# PMOD_RS485.net
KiCad netlist of a schematic drawn in Altium Designer
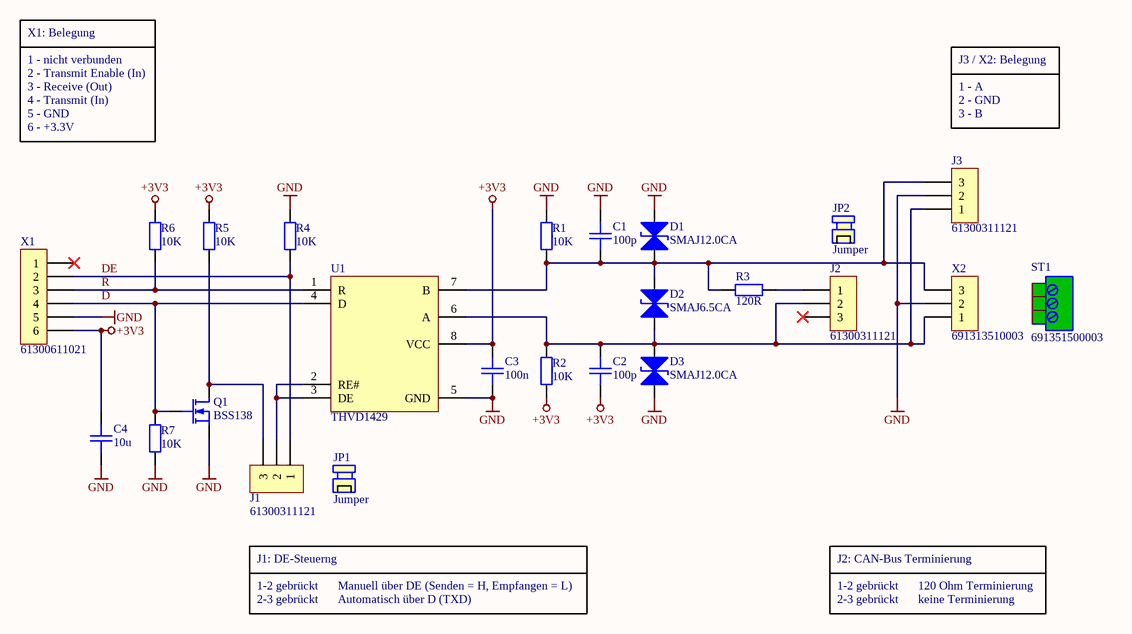
[diagram p0: PMOD_RS485.SchDoc]

(export (version "E")
  (design (tool "Eeschema 10.0.6"))
  (components
    (comp (ref "C1")
      (value "100p")
      (footprint "0805-C")
      (description "CAP CER 100PF 250V C0G/NP0 0805")
      (fields
        (field (name "MANUFACTURER PARTNO") "GRM21A5C2E101FW01D")
        (field (name "MANUFACTURER") "Murata Electronics")
      )
      (libsource (lib "Dual-CAN-HAT") (part "Capacitor 100p 0805"))
    )
    (comp (ref "C2")
      (value "100p")
      (footprint "0805-C")
      (description "CAP CER 100PF 250V C0G/NP0 0805")
      (fields
        (field (name "MANUFACTURER PARTNO") "GRM21A5C2E101FW01D")
        (field (name "MANUFACTURER") "Murata Electronics")
      )
      (libsource (lib "Dual-CAN-HAT") (part "Capacitor 100p 0805"))
    )
    (comp (ref "C3")
      (value "100n")
      (footprint "0805-C")
      (description "CAP CER 0.1UF 50V X8R 0805")
      (fields
        (field (name "MANUFACTURER PARTNO") "GCM21BR91H104KA37L")
        (field (name "MANUFACTURER") "Murata Electronics")
      )
      (libsource (lib "Dual-CAN-HAT") (part "Capacitor 100n 0805"))
    )
    (comp (ref "C4")
      (value "10u")
      (footprint "0805-C")
      (description "CAP CER 10UF 16V X5R 0805")
      (fields
        (field (name "MANUFACTURER PARTNO") "EMK212BBJ106KGHT")
        (field (name "MANUFACTURER") "Taiyo Yuden")
      )
      (libsource (lib "Dual-CAN-HAT") (part "Capacitor 10u 0805"))
    )
    (comp (ref "D1")
      (value "SMAJ12.0CA")
      (footprint "SMA-BIDIRECTIONAL")
      (description "TVS DIODE 12V 19.9V DO214AC")
      (fields
        (field (name "MANUFACTURER PARTNO") "SMAJ12CA-TP")
        (field (name "MANUFACTURER") "Micro Commercial Co")
      )
      (libsource (lib "Dual-CAN-HAT") (part "Diode TVS SMAJ12.0CA"))
    )
    (comp (ref "D2")
      (value "SMAJ6.5CA")
      (footprint "SMA-BIDIRECTIONAL")
      (description "TVS DIODE 6.5V 11.2V DO214AC")
      (fields
        (field (name "MANUFACTURER PARTNO") "SMAJ6.5CA-TP")
        (field (name "MANUFACTURER") "Micro Commercial Co")
      )
      (libsource (lib "Dual-CAN-HAT") (part "Diode TVS SMAJ6.5CA"))
    )
    (comp (ref "D3")
      (value "SMAJ12.0CA")
      (footprint "SMA-BIDIRECTIONAL")
      (description "TVS DIODE 12V 19.9V DO214AC")
      (fields
        (field (name "MANUFACTURER PARTNO") "SMAJ12CA-TP")
        (field (name "MANUFACTURER") "Micro Commercial Co")
      )
      (libsource (lib "Dual-CAN-HAT") (part "Diode TVS SMAJ12.0CA"))
    )
    (comp (ref "J1")
      (value "61300311121")
      (footprint "WE-61300311121")
      (description "CONN HEADER VERT 3POS 2.54MM")
      (fields (field (name "MANUFACTURER") "Würth Elektronik"))
      (libsource (lib "CAN_RS485_BREAKOUT") (part "WE 61300311121"))
    )
    (comp (ref "J2")
      (value "61300311121")
      (footprint "WE-61300311121")
      (description "CONN HEADER VERT 3POS 2.54MM")
      (fields (field (name "MANUFACTURER") "Würth Elektronik"))
      (libsource (lib "") (part "WE 61300311121_2"))
    )
    (comp (ref "J3")
      (value "61300311121")
      (footprint "WE-61300311121")
      (description "CONN HEADER VERT 3POS 2.54MM")
      (fields (field (name "MANUFACTURER") "Würth Elektronik"))
      (libsource (lib "") (part "WE 61300311121_1"))
    )
    (comp (ref "JP1")
      (value "Jumper")
      (description "JUMPER W/TEST PNT 1X2PINS 2.54MM")
      (fields
        (field (name "MANUFACTURER") "Würth Elektronik")
        (field (name "MANUFACTURER PARTNO") "60900213421")
      )
      (libsource (lib "Dual-CAN-HAT") (part "Jumper"))
    )
    (comp (ref "JP2")
      (value "Jumper")
      (description "JUMPER W/TEST PNT 1X2PINS 2.54MM")
      (fields
        (field (name "MANUFACTURER") "Würth Elektronik")
        (field (name "MANUFACTURER PARTNO") "60900213421")
      )
      (libsource (lib "Dual-CAN-HAT") (part "Jumper"))
    )
    (comp (ref "Q1")
      (value "BSS138")
      (footprint "SOT23-3")
      (description "MOSFET N-CH 50V 200MA SOT-23")
      (fields
        (field (name "MANUFACTURER") "ON Semiconductor")
        (field (name "MANUFACTURER PARTNO") "BSS138LT3G")
      )
      (libsource (lib "obu2.0_mriboard") (part "Transistor BSS138"))
    )
    (comp (ref "R1")
      (value "10K")
      (footprint "0805-R")
      (description "RES SMD 10K OHM 1% 1/8W 0805")
      (fields (field (name "MANUFACTURER") "Yageo") (field (name "MANUFACTURER PARTNO") "RC0805FR-0710KL"))
      (libsource (lib "Dual-CAN-HAT") (part "Resistor 10K 0805"))
    )
    (comp (ref "R2")
      (value "10K")
      (footprint "0805-R")
      (description "RES SMD 10K OHM 1% 1/8W 0805")
      (fields (field (name "MANUFACTURER") "Yageo") (field (name "MANUFACTURER PARTNO") "RC0805FR-0710KL"))
      (libsource (lib "Dual-CAN-HAT") (part "Resistor 10K 0805"))
    )
    (comp (ref "R3")
      (value "120R")
      (footprint "1206-R")
      (description "RES SMD 120 OHM 1% 1/4W 1206")
      (fields (field (name "MANUFACTURER") "Yageo") (field (name "MANUFACTURER PARTNO") "RC1206FR-07120RL"))
      (libsource (lib "CAN_RS485_BREAKOUT") (part "Resistor 120R 1206"))
    )
    (comp (ref "R4")
      (value "10K")
      (footprint "0805-R")
      (description "RES SMD 10K OHM 1% 1/8W 0805")
      (fields (field (name "MANUFACTURER") "Yageo") (field (name "MANUFACTURER PARTNO") "RC0805FR-0710KL"))
      (libsource (lib "") (part "Resistor 10K 0805_1"))
    )
    (comp (ref "R5")
      (value "10K")
      (footprint "0805-R")
      (description "RES SMD 10K OHM 1% 1/8W 0805")
      (fields (field (name "MANUFACTURER") "Yageo") (field (name "MANUFACTURER PARTNO") "RC0805FR-0710KL"))
      (libsource (lib "") (part "Resistor 10K 0805_1"))
    )
    (comp (ref "R6")
      (value "10K")
      (footprint "0805-R")
      (description "RES SMD 10K OHM 1% 1/8W 0805")
      (fields (field (name "MANUFACTURER") "Yageo") (field (name "MANUFACTURER PARTNO") "RC0805FR-0710KL"))
      (libsource (lib "Dual-CAN-HAT") (part "Resistor 10K 0805"))
    )
    (comp (ref "R7")
      (value "10K")
      (footprint "0805-R")
      (description "RES SMD 10K OHM 1% 1/8W 0805")
      (fields (field (name "MANUFACTURER") "Yageo") (field (name "MANUFACTURER PARTNO") "RC0805FR-0710KL"))
      (libsource (lib "") (part "Resistor 10K 0805_1"))
    )
    (comp (ref "ST1")
      (value "691351500003")
      (description "TERM BLOCK PLUG 3POS 5.08MM")
      (fields (field (name "MANUFACTURER") "Würth Elektronik"))
      (libsource (lib "Dual-CAN-HAT") (part "Plug WE 691351500003"))
    )
    (comp (ref "U1")
      (value "THVD1429")
      (footprint "SOIC-8")
      (description "IC TRANSCEIVER HALF 1/1 8SOIC")
      (fields
        (field (name "MANUFACTURER") "Texas Instruments")
        (field (name "MANUFACTURER PARTNO") "THVD1429DR")
      )
      (libsource (lib "CAN_RS485_BREAKOUT") (part "THVD1429 SOIC8"))
    )
    (comp (ref "X1")
      (value "61300611021")
      (footprint "WE-61302021121")
      (description "CONN HEADER R/A 6POS 2.54MM")
      (fields (field (name "MANUFACTURER") "Würth Elektronik"))
      (libsource (lib "CAN_RS485_BREAKOUT") (part "PMOD Plug 6X1"))
    )
    (comp (ref "X2")
      (value "691313510003")
      (footprint "WE-691313510003")
      (description "TERM BLOCK HDR 3POS 90DEG 5.08MM")
      (fields (field (name "MANUFACTURER") "Würth Elektronik"))
      (libsource (lib "CAN_RS485_BREAKOUT") (part "WE 691313510003"))
    )
  )
  (nets
    (net (code "1") (name "+3V3") (class "Default")
      (node (ref "C2") (pin "2") (pinfunction "2_2") (pintype "passive"))
      (node (ref "C3") (pin "1") (pinfunction "1_1") (pintype "passive"))
      (node (ref "C4") (pin "2") (pinfunction "2_2") (pintype "passive"))
      (node (ref "R2") (pin "2") (pinfunction "2_2") (pintype "passive"))
      (node (ref "R5") (pin "2") (pinfunction "2_2") (pintype "passive"))
      (node (ref "R6") (pin "1") (pinfunction "1_1") (pintype "passive"))
      (node (ref "U1") (pin "8") (pinfunction "VCC_8") (pintype "power_in"))
      (node (ref "X1") (pin "6") (pinfunction "6_6") (pintype "passive"))
    )
    (net (code "2") (name "/D") (class "Default")
      (node (ref "Q1") (pin "1") (pinfunction "Gate_1") (pintype "passive"))
      (node (ref "R7") (pin "2") (pinfunction "2_2") (pintype "passive"))
      (node (ref "U1") (pin "4") (pinfunction "D_4") (pintype "passive"))
      (node (ref "X1") (pin "4") (pinfunction "4_4") (pintype "passive"))
    )
    (net (code "3") (name "/DE") (class "Default")
      (node (ref "J1") (pin "1") (pinfunction "1_1") (pintype "passive"))
      (node (ref "R4") (pin "1") (pinfunction "1_1") (pintype "passive"))
      (node (ref "X1") (pin "2") (pinfunction "2_2") (pintype "passive"))
    )
    (net (code "4") (name "/R") (class "Default")
      (node (ref "R6") (pin "2") (pinfunction "2_2") (pintype "passive"))
      (node (ref "U1") (pin "1") (pinfunction "R_1") (pintype "passive"))
      (node (ref "X1") (pin "3") (pinfunction "3_3") (pintype "passive"))
    )
    (net (code "5") (name "GND") (class "Default")
      (node (ref "C1") (pin "1") (pinfunction "1_1") (pintype "passive"))
      (node (ref "C3") (pin "2") (pinfunction "2_2") (pintype "passive"))
      (node (ref "C4") (pin "1") (pinfunction "1_1") (pintype "passive"))
      (node (ref "D1") (pin "1") (pinfunction "A1_1") (pintype "passive"))
      (node (ref "D3") (pin "2") (pinfunction "A2_2") (pintype "passive"))
      (node (ref "J3") (pin "2") (pinfunction "2_2") (pintype "passive"))
      (node (ref "Q1") (pin "2") (pinfunction "Source_2") (pintype "passive"))
      (node (ref "R1") (pin "1") (pinfunction "1_1") (pintype "passive"))
      (node (ref "R4") (pin "2") (pinfunction "2_2") (pintype "passive"))
      (node (ref "R7") (pin "1") (pinfunction "1_1") (pintype "passive"))
      (node (ref "U1") (pin "5") (pinfunction "GND_5") (pintype "power_in"))
      (node (ref "X1") (pin "5") (pinfunction "5_5") (pintype "passive"))
      (node (ref "X2") (pin "2") (pinfunction "2_2") (pintype "passive"))
    )
    (net (code "6") (name "Net-(D1-A2)") (class "Default")
      (node (ref "C1") (pin "2") (pinfunction "2_2") (pintype "passive"))
      (node (ref "D1") (pin "2") (pinfunction "A2_2") (pintype "passive"))
      (node (ref "D2") (pin "1") (pinfunction "A1_1") (pintype "passive"))
      (node (ref "J3") (pin "3") (pinfunction "3_3") (pintype "passive"))
      (node (ref "R1") (pin "2") (pinfunction "2_2") (pintype "passive"))
      (node (ref "R3") (pin "1") (pinfunction "1_1") (pintype "passive"))
      (node (ref "U1") (pin "7") (pinfunction "B_7") (pintype "passive"))
      (node (ref "X2") (pin "3") (pinfunction "3_3") (pintype "passive"))
    )
    (net (code "7") (name "Net-(D2-A2)") (class "Default")
      (node (ref "C2") (pin "1") (pinfunction "1_1") (pintype "passive"))
      (node (ref "D2") (pin "2") (pinfunction "A2_2") (pintype "passive"))
      (node (ref "D3") (pin "1") (pinfunction "A1_1") (pintype "passive"))
      (node (ref "J2") (pin "2") (pinfunction "2_2") (pintype "passive"))
      (node (ref "J3") (pin "1") (pinfunction "1_1") (pintype "passive"))
      (node (ref "R2") (pin "1") (pinfunction "1_1") (pintype "passive"))
      (node (ref "U1") (pin "6") (pinfunction "A_6") (pintype "passive"))
      (node (ref "X2") (pin "1") (pinfunction "1_1") (pintype "passive"))
    )
    (net (code "8") (name "Net-(J2-Pad1)") (class "Default")
      (node (ref "J2") (pin "1") (pinfunction "1_1") (pintype "passive"))
      (node (ref "R3") (pin "2") (pinfunction "2_2") (pintype "passive"))
    )
    (net (code "9") (name "Net-(Q1-Drain)") (class "Default")
      (node (ref "J1") (pin "3") (pinfunction "3_3") (pintype "passive"))
      (node (ref "Q1") (pin "3") (pinfunction "Drain_3") (pintype "passive"))
      (node (ref "R5") (pin "1") (pinfunction "1_1") (pintype "passive"))
    )
    (net (code "10") (name "Net-(U1-DE)") (class "Default")
      (node (ref "J1") (pin "2") (pinfunction "2_2") (pintype "passive"))
      (node (ref "U1") (pin "2") (pinfunction "RE#_2") (pintype "passive"))
      (node (ref "U1") (pin "3") (pinfunction "DE_3") (pintype "passive"))
    )
    (net (code "11") (name "unconnected-(J2-Pad3)") (class "Default")
      (node (ref "J2") (pin "3") (pinfunction "3_3") (pintype "passive+no_connect"))
    )
    (net (code "12") (name "unconnected-(X1-Pad1)") (class "Default")
      (node (ref "X1") (pin "1") (pinfunction "1_1") (pintype "passive+no_connect"))
    )
  )
)
